# OM-02P.net
KiCad netlist of a schematic drawn in Altium Designer
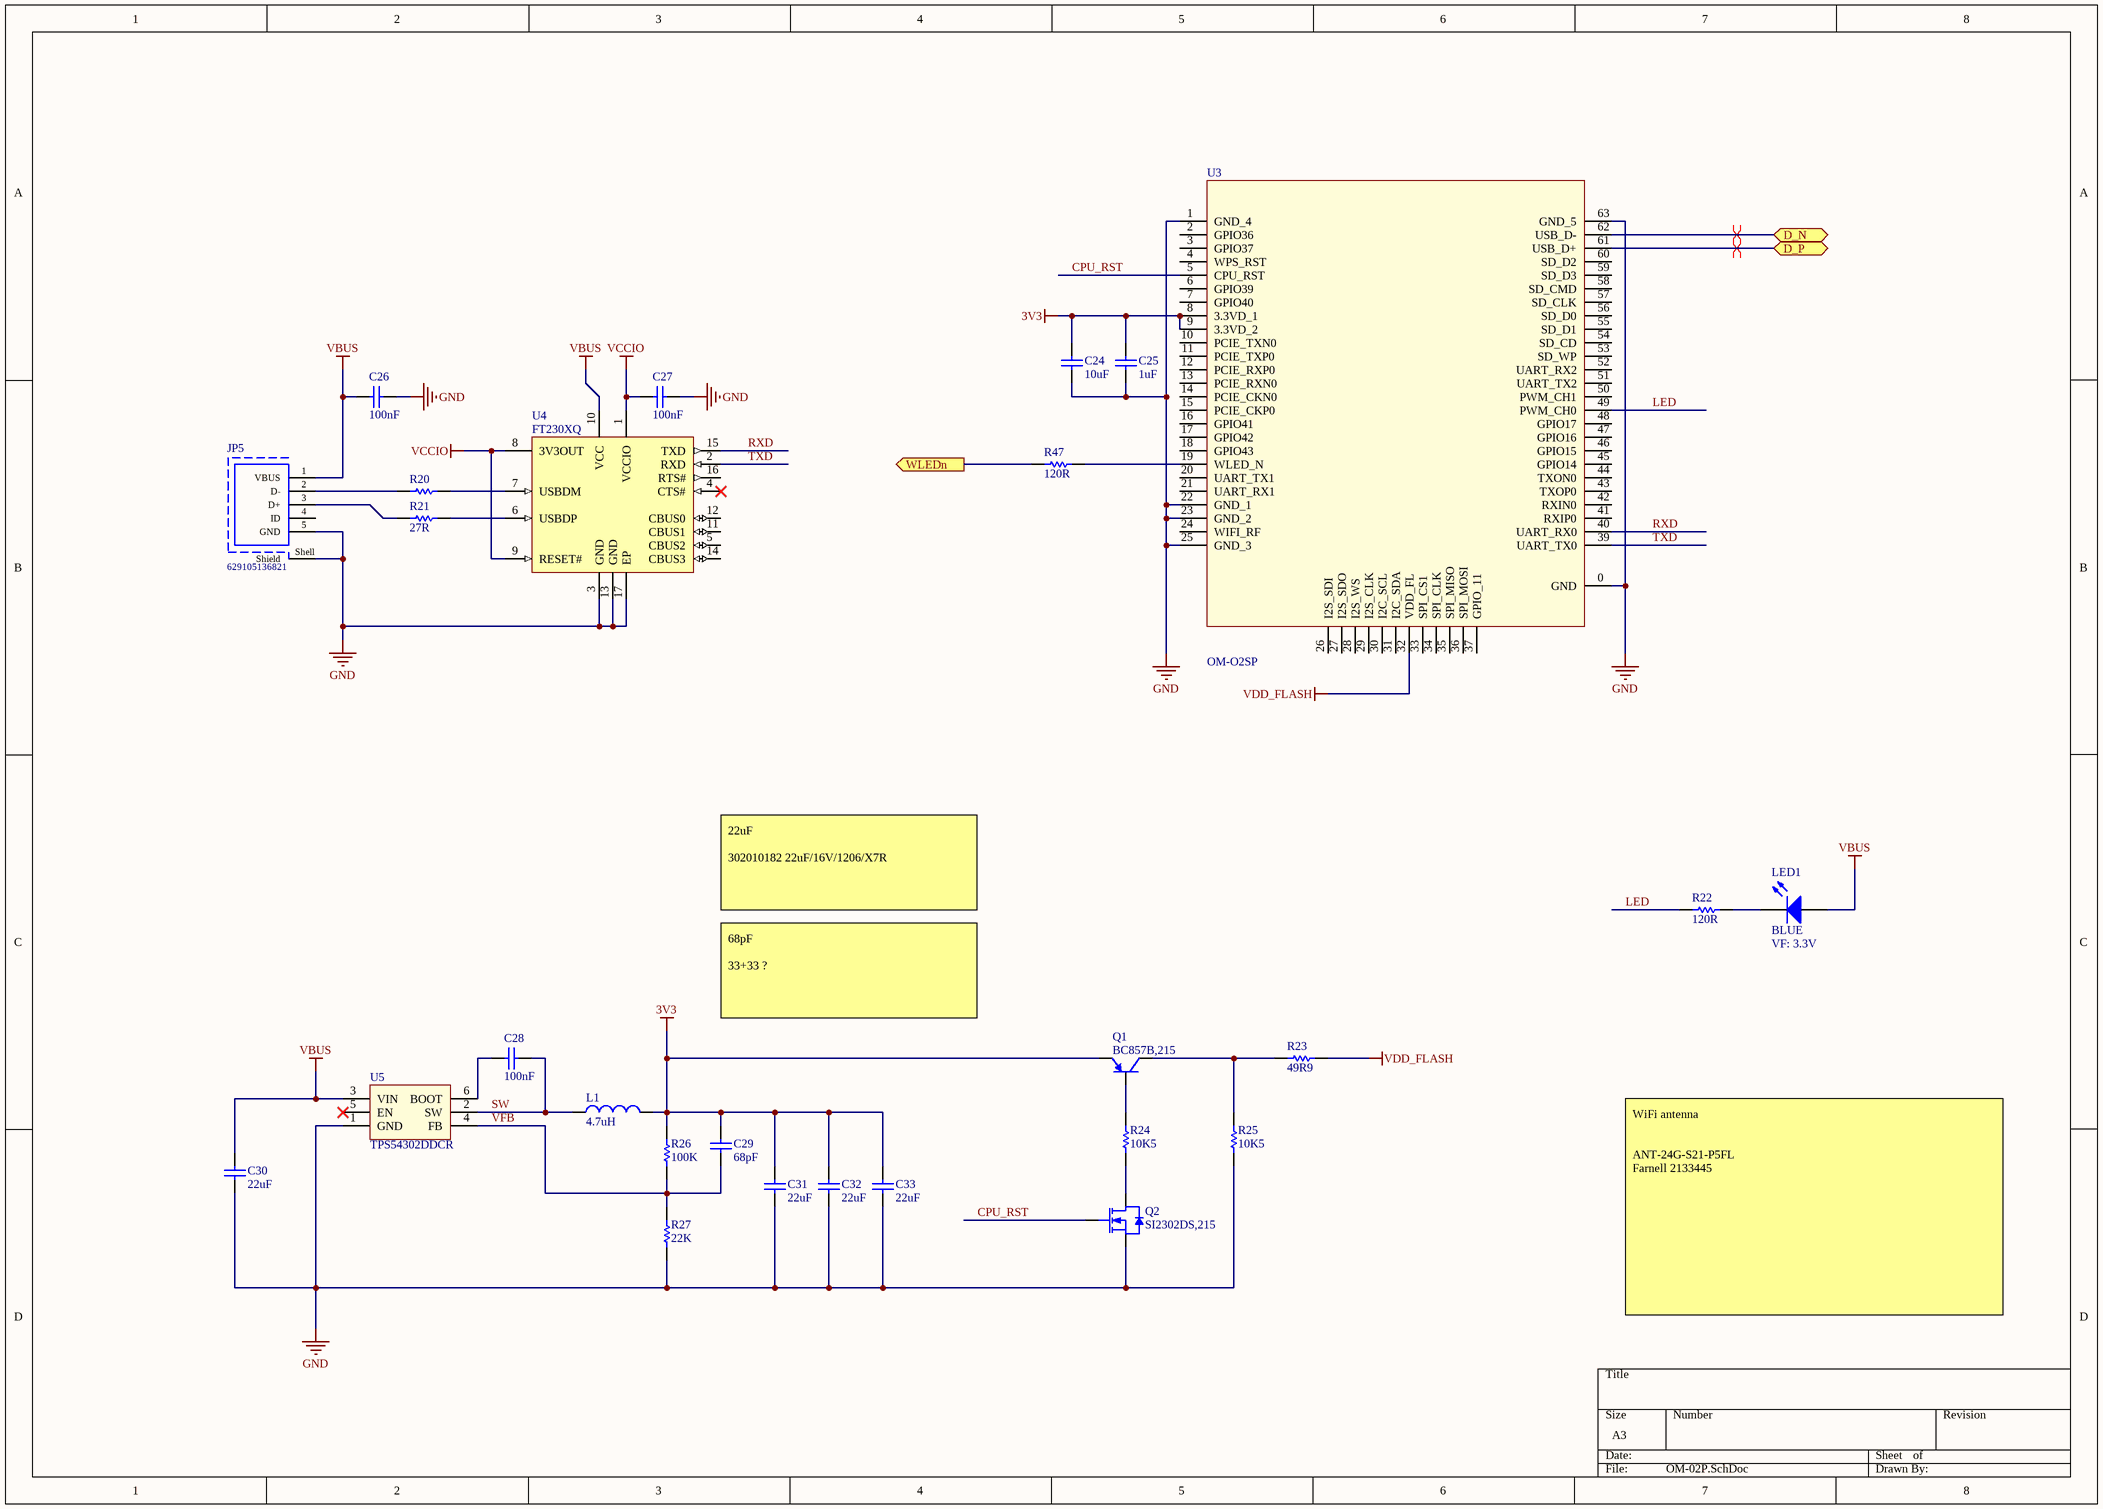
[diagram p0: OM-02P.SchDoc]

(export (version "E")
  (design (tool "Eeschema 10.0.6"))
  (components
    (comp (ref "C24")
      (value "10uF")
      (footprint "CAPC0603(1608)55_L")
      (description "0603 10uF ±20% 6.3V X5R H=0.8mm")
      (fields (field (name "MPN") "CL10A106MQ8NNNC") (field (name "VOLTAGE") "10V"))
      (libsource (lib "seeed") (part "CAP_10uF_0603"))
    )
    (comp (ref "C25")
      (value "1uF")
      (footprint "CAPC0402(1005)33_L")
      (description "0402 1μF ±10% 16V X5R")
      (fields (field (name "MPN") "GRM155R61C105KA12D") (field (name "VOLTAGE") "10V"))
      (libsource (lib "seeed") (part "CAP_1uF_0402"))
    )
    (comp (ref "C26")
      (value "100nF")
      (footprint "CAPC0402(1005)33_L")
      (description "0402 100nF ±10% 16V X5R")
      (fields (field (name "MPN") "GRM155R61C104KA88D") (field (name "VOLTAGE") "16V"))
      (libsource (lib "seeed") (part "CAP_100nF_0402"))
    )
    (comp (ref "C27")
      (value "100nF")
      (footprint "CAPC0402(1005)33_L")
      (description "0402 100nF ±10% 16V X5R")
      (fields (field (name "MPN") "GRM155R61C104KA88D") (field (name "VOLTAGE") "16V"))
      (libsource (lib "seeed") (part "CAP_100nF_0402"))
    )
    (comp (ref "C28")
      (value "100nF")
      (footprint "CAPC0402(1005)33_L")
      (description "0402 100nF ±10% 16V X5R")
      (fields (field (name "MPN") "GRM155R61C104KA88D") (field (name "VOLTAGE") "16V"))
      (libsource (lib "seeed") (part "CAP_100nF_0402"))
    )
    (comp (ref "C29")
      (value "68pF")
      (footprint "CAPC0402(1005)33_L")
      (description "0402 68pF ±5% 50V C0G")
      (fields (field (name "MPN") "GRM1555C1H680JA01D") (field (name "VOLTAGE") "50V"))
      (libsource (lib "seeed") (part "CAP_68pF_0402"))
    )
    (comp (ref "C30")
      (value "22uF")
      (footprint "CAPC1206(3216)75_L")
      (description "1206 22uF ±10% 16V X5R")
      (fields (field (name "MPN") "CL31A226KOHNNNE") (field (name "VOLTAGE") "16V"))
      (libsource (lib "seeed") (part "CAP_22uF_16V_1206"))
    )
    (comp (ref "C31")
      (value "22uF")
      (footprint "CAPC1206(3216)75_L")
      (description "1206 22uF ±10% 16V X5R")
      (fields (field (name "MPN") "CL31A226KOHNNNE") (field (name "VOLTAGE") "16V"))
      (libsource (lib "seeed") (part "CAP_22uF_16V_1206"))
    )
    (comp (ref "C32")
      (value "22uF")
      (footprint "CAPC1206(3216)75_L")
      (description "1206 22uF ±10% 16V X5R")
      (fields (field (name "MPN") "CL31A226KOHNNNE") (field (name "VOLTAGE") "16V"))
      (libsource (lib "seeed") (part "CAP_22uF_16V_1206"))
    )
    (comp (ref "C33")
      (value "22uF")
      (footprint "CAPC1206(3216)75_L")
      (description "1206 22uF ±10% 16V X5R")
      (fields (field (name "MPN") "CL31A226KOHNNNE") (field (name "VOLTAGE") "16V"))
      (libsource (lib "seeed") (part "CAP_22uF_16V_1206"))
    )
    (comp (ref "JP5")
      (value "629105136821")
      (footprint "629105136821")
      (description "Micro USB 2.0 Type B Receptacle WR-COM, Horizontal, SMT, with Pads and Pegs")
      (fields (field (name "PUBLISHER") "Wurth Elektronik"))
      (libsource (lib "ALTIUM-WR-COM_USB_20-rev18d") (part "629105136821"))
    )
    (comp (ref "L1")
      (value "4.7uH")
      (footprint "L_6045")
      (description "6.0*6.0*4.5 4.7μH ±20% 5.50A DCR=0.034 SRF=24MHz")
      (fields (field (name "MPN") "SWPA6045S4R7MT"))
      (libsource (lib "seeed") (part "L_4.7uH_6045"))
    )
    (comp (ref "LED1")
      (value "BLUE")
      (footprint "LED_APA3010x")
      (description "LED BLUE")
      (fields (field (name "MPN") "APA3010QBC/D-GX") (field (name "VF") "3.3V"))
      (libsource (lib "seeed") (part "LED-BLUE-APA3010QBC/D-GX"))
    )
    (comp (ref "Q1")
      (value "BC857B,215")
      (footprint "NXP-SOT23_L")
      (description "PNP,Vce=45V,Ic=0.1A,hfe=220~475")
      (fields (field (name "MANUFACTURER") "Infineon"))
      (libsource (lib "seeed") (part "BC857"))
    )
    (comp (ref "Q2")
      (value "SI2302DS,215")
      (footprint "NXP-SOT23_L")
      (description "N-Channel Enhancement Mode Field-Effect Transistor, 20 V, 2.5 A, 3-Pin SOT23, Tape and Reel")
      (fields (field (name "MANUFACTURER") "NXP Semiconductors") (field (name "MPN") "SI2302CDS-T1-GE3"))
      (libsource (lib "seeed") (part "SI2302"))
    )
    (comp (ref "R20")
      (value "27R")
      (footprint "RESC0402(1005)_L")
      (description "0402 27Ω ±1% 1/16W")
      (fields (field (name "TOLERANCE") "1%") (field (name "POWER") "62.5mW"))
      (libsource (lib "seeed") (part "RES_27R_0402"))
    )
    (comp (ref "R21")
      (value "27R")
      (footprint "RESC0402(1005)_L")
      (description "0402 27Ω ±1% 1/16W")
      (fields (field (name "TOLERANCE") "1%") (field (name "POWER") "62.5mW"))
      (libsource (lib "seeed") (part "RES_27R_0402"))
    )
    (comp (ref "R22")
      (value "120R")
      (footprint "RESC0402(1005)_L")
      (description "0402 120Ω ±1% 1/16W")
      (fields (field (name "TOLERANCE") "1%") (field (name "POWER") "62.5mW"))
      (libsource (lib "seeed") (part "RES_120R_0402"))
    )
    (comp (ref "R23")
      (value "49R9")
      (footprint "RESC0402(1005)_L")
      (description "0402 49.9Ω ±1% 1/16W")
      (fields (field (name "TOLERANCE") "1%") (field (name "POWER") "62.5mW"))
      (libsource (lib "seeed") (part "RES_49R9_0402"))
    )
    (comp (ref "R24")
      (value "10K5")
      (footprint "RESC0402(1005)_L")
      (description "0402 10.5KΩ ±1% 1/16W")
      (fields (field (name "TOLERANCE") "1%") (field (name "POWER") "62.5mW"))
      (libsource (lib "seeed") (part "RES_10K5_0402"))
    )
    (comp (ref "R25")
      (value "10K5")
      (footprint "RESC0402(1005)_L")
      (description "0402 10.5KΩ ±1% 1/16W")
      (fields (field (name "TOLERANCE") "1%") (field (name "POWER") "62.5mW"))
      (libsource (lib "seeed") (part "RES_10K5_0402"))
    )
    (comp (ref "R26")
      (value "100K")
      (footprint "RESC0402(1005)_L")
      (description "0402 100KΩ ±1% 1/16W")
      (fields (field (name "TOLERANCE") "1%") (field (name "POWER") "62.5mW"))
      (libsource (lib "seeed") (part "RES_100K_0402"))
    )
    (comp (ref "R27")
      (value "22K")
      (footprint "RESC0402(1005)_L")
      (description "0402 22KΩ ±1% 1/16W")
      (fields (field (name "TOLERANCE") "1%") (field (name "POWER") "62.5mW"))
      (libsource (lib "seeed") (part "RES_22K_0402"))
    )
    (comp (ref "R47")
      (value "120R")
      (footprint "RESC0402(1005)_L")
      (description "0402 120Ω ±1% 1/16W")
      (fields (field (name "TOLERANCE") "1%") (field (name "POWER") "62.5mW"))
      (libsource (lib "seeed") (part "RES_120R_0402"))
    )
    (comp (ref "U3")
      (value "OM-O2SP")
      (footprint "CPU-OM-O2S")
      (description "Onion Omega2S")
      (libsource (lib "micun") (part "CPU-OM-O2SP"))
    )
    (comp (ref "U4")
      (value "FT230XQ")
      (footprint "QFN-16_N")
      (description "USB Bridge, USB to UART USB 2.0 UART Interface 16-QFN (4x4)")
      (fields (field (name "MPN") "FT230XQ-R"))
      (libsource (lib "micun") (part "IC-COM-USB-FT230XQ-SQ17"))
    )
    (comp (ref "U5")
      (value "TPS54302DDCR")
      (footprint "FAIR-MA06A_V")
      (description "Buck Switching Regulator IC Positive Adjustable 0.596V 1 Output 3A SOT-23-6 Thin, TSOT-23-6")
      (libsource (lib "seeed") (part "TPS54302DDCR"))
    )
  )
  (nets
    (net (code "1") (name "/CPU_RST") (class "Default")
      (node (ref "Q2") (pin "1") (pinfunction "G_1") (pintype "passive"))
      (node (ref "U3") (pin "5") (pinfunction "CPU_RST_5") (pintype "passive"))
    )
    (net (code "2") (name "/D_N") (class "Default")
      (node (ref "U3") (pin "62") (pinfunction "USB_D-_62") (pintype "passive"))
    )
    (net (code "3") (name "/D_P") (class "Default")
      (node (ref "U3") (pin "61") (pinfunction "USB_D+_61") (pintype "passive"))
    )
    (net (code "4") (name "/LED") (class "Default")
      (node (ref "R22") (pin "1") (pinfunction "1_1") (pintype "passive"))
      (node (ref "U3") (pin "49") (pinfunction "PWM_CH0_49") (pintype "passive"))
    )
    (net (code "5") (name "/RXD") (class "Default")
      (node (ref "U3") (pin "40") (pinfunction "UART_RX0_40") (pintype "passive"))
      (node (ref "U4") (pin "15") (pinfunction "TXD_15") (pintype "output"))
    )
    (net (code "6") (name "/SW") (class "Default")
      (node (ref "C28") (pin "2") (pinfunction "2_2") (pintype "passive"))
      (node (ref "L1") (pin "1") (pinfunction "1_1") (pintype "passive"))
      (node (ref "U5") (pin "2") (pinfunction "SW_2") (pintype "passive"))
    )
    (net (code "7") (name "/TXD") (class "Default")
      (node (ref "U3") (pin "39") (pinfunction "UART_TX0_39") (pintype "passive"))
      (node (ref "U4") (pin "2") (pinfunction "RXD_2") (pintype "input"))
    )
    (net (code "8") (name "/VFB") (class "Default")
      (node (ref "C29") (pin "1") (pinfunction "1_1") (pintype "passive"))
      (node (ref "R26") (pin "1") (pinfunction "1_1") (pintype "passive"))
      (node (ref "R27") (pin "2") (pinfunction "2_2") (pintype "passive"))
      (node (ref "U5") (pin "4") (pinfunction "FB_4") (pintype "passive"))
    )
    (net (code "9") (name "/WLEDn") (class "Default")
      (node (ref "R47") (pin "1") (pinfunction "1_1") (pintype "passive"))
    )
    (net (code "10") (name "3V3") (class "Default")
      (node (ref "C24") (pin "2") (pinfunction "2_2") (pintype "passive"))
      (node (ref "C25") (pin "2") (pinfunction "2_2") (pintype "passive"))
      (node (ref "C29") (pin "2") (pinfunction "2_2") (pintype "passive"))
      (node (ref "C31") (pin "2") (pinfunction "2_2") (pintype "passive"))
      (node (ref "C32") (pin "2") (pinfunction "2_2") (pintype "passive"))
      (node (ref "C33") (pin "2") (pinfunction "2_2") (pintype "passive"))
      (node (ref "L1") (pin "2") (pinfunction "2_2") (pintype "passive"))
      (node (ref "Q1") (pin "2") (pinfunction "E_2") (pintype "passive"))
      (node (ref "R26") (pin "2") (pinfunction "2_2") (pintype "passive"))
      (node (ref "U3") (pin "8") (pinfunction "3.3VD_1_8") (pintype "power_in"))
      (node (ref "U3") (pin "9") (pinfunction "3.3VD_2_9") (pintype "power_in"))
    )
    (net (code "11") (name "GND") (class "Default")
      (node (ref "C24") (pin "1") (pinfunction "1_1") (pintype "passive"))
      (node (ref "C25") (pin "1") (pinfunction "1_1") (pintype "passive"))
      (node (ref "C26") (pin "2") (pinfunction "2_2") (pintype "passive"))
      (node (ref "C27") (pin "2") (pinfunction "2_2") (pintype "passive"))
      (node (ref "C30") (pin "1") (pinfunction "1_1") (pintype "passive"))
      (node (ref "C31") (pin "1") (pinfunction "1_1") (pintype "passive"))
      (node (ref "C32") (pin "1") (pinfunction "1_1") (pintype "passive"))
      (node (ref "C33") (pin "1") (pinfunction "1_1") (pintype "passive"))
      (node (ref "JP5") (pin "5") (pinfunction "GND_5") (pintype "passive"))
      (node (ref "JP5") (pin "Shell") (pinfunction "Shield_Shell") (pintype "passive"))
      (node (ref "Q2") (pin "2") (pinfunction "S_2") (pintype "passive"))
      (node (ref "R25") (pin "1") (pinfunction "1_1") (pintype "passive"))
      (node (ref "R27") (pin "1") (pinfunction "1_1") (pintype "passive"))
      (node (ref "U3") (pin "0") (pinfunction "GND_0") (pintype "passive"))
      (node (ref "U3") (pin "1") (pinfunction "GND_4_1") (pintype "power_in"))
      (node (ref "U3") (pin "22") (pinfunction "GND_1_22") (pintype "power_in"))
      (node (ref "U3") (pin "23") (pinfunction "GND_2_23") (pintype "power_in"))
      (node (ref "U3") (pin "25") (pinfunction "GND_3_25") (pintype "power_in"))
      (node (ref "U3") (pin "63") (pinfunction "GND_5_63") (pintype "power_in"))
      (node (ref "U4") (pin "13") (pinfunction "GND_13") (pintype "power_in"))
      (node (ref "U4") (pin "17") (pinfunction "EP_17") (pintype "power_in"))
      (node (ref "U4") (pin "3") (pinfunction "GND_3") (pintype "power_in"))
      (node (ref "U5") (pin "1") (pinfunction "GND_1") (pintype "power_in"))
    )
    (net (code "12") (name "Net-(JP5-D+)") (class "Default")
      (node (ref "JP5") (pin "3") (pinfunction "D+_3") (pintype "passive"))
      (node (ref "R21") (pin "1") (pinfunction "1_1") (pintype "passive"))
    )
    (net (code "13") (name "Net-(JP5-D-)") (class "Default")
      (node (ref "JP5") (pin "2") (pinfunction "D-_2") (pintype "passive"))
      (node (ref "R20") (pin "1") (pinfunction "1_1") (pintype "passive"))
    )
    (net (code "14") (name "Net-(LED1-K)") (class "Default")
      (node (ref "LED1") (pin "1") (pinfunction "K_1") (pintype "passive"))
      (node (ref "R22") (pin "2") (pinfunction "2_2") (pintype "passive"))
    )
    (net (code "15") (name "Net-(Q1-B)") (class "Default")
      (node (ref "Q1") (pin "1") (pinfunction "B_1") (pintype "passive"))
      (node (ref "R24") (pin "2") (pinfunction "2_2") (pintype "passive"))
    )
    (net (code "16") (name "Net-(Q1-C)") (class "Default")
      (node (ref "Q1") (pin "3") (pinfunction "C_3") (pintype "passive"))
      (node (ref "R23") (pin "1") (pinfunction "1_1") (pintype "passive"))
      (node (ref "R25") (pin "2") (pinfunction "2_2") (pintype "passive"))
    )
    (net (code "17") (name "Net-(Q2-D)") (class "Default")
      (node (ref "Q2") (pin "3") (pinfunction "D_3") (pintype "passive"))
      (node (ref "R24") (pin "1") (pinfunction "1_1") (pintype "passive"))
    )
    (net (code "18") (name "Net-(U3-WLED_N)") (class "Default")
      (node (ref "R47") (pin "2") (pinfunction "2_2") (pintype "passive"))
      (node (ref "U3") (pin "19") (pinfunction "WLED_N_19") (pintype "passive"))
    )
    (net (code "19") (name "Net-(U4-USBDM)") (class "Default")
      (node (ref "R20") (pin "2") (pinfunction "2_2") (pintype "passive"))
      (node (ref "U4") (pin "7") (pinfunction "USBDM_7") (pintype "input"))
    )
    (net (code "20") (name "Net-(U4-USBDP)") (class "Default")
      (node (ref "R21") (pin "2") (pinfunction "2_2") (pintype "passive"))
      (node (ref "U4") (pin "6") (pinfunction "USBDP_6") (pintype "input"))
    )
    (net (code "21") (name "Net-(U5-BOOT)") (class "Default")
      (node (ref "C28") (pin "1") (pinfunction "1_1") (pintype "passive"))
      (node (ref "U5") (pin "6") (pinfunction "BOOT_6") (pintype "power_in"))
    )
    (net (code "22") (name "VBUS") (class "Default")
      (node (ref "C26") (pin "1") (pinfunction "1_1") (pintype "passive"))
      (node (ref "C30") (pin "2") (pinfunction "2_2") (pintype "passive"))
      (node (ref "JP5") (pin "1") (pinfunction "VBUS_1") (pintype "passive"))
      (node (ref "LED1") (pin "2") (pinfunction "A_2") (pintype "passive"))
      (node (ref "U4") (pin "10") (pinfunction "VCC_10") (pintype "power_in"))
      (node (ref "U5") (pin "3") (pinfunction "VIN_3") (pintype "power_in"))
    )
    (net (code "23") (name "VCCIO") (class "Default")
      (node (ref "C27") (pin "1") (pinfunction "1_1") (pintype "passive"))
      (node (ref "U4") (pin "1") (pinfunction "VCCIO_1") (pintype "power_in"))
      (node (ref "U4") (pin "8") (pinfunction "3V3OUT_8") (pintype "power_in"))
      (node (ref "U4") (pin "9") (pinfunction "RESET#_9") (pintype "input"))
    )
    (net (code "24") (name "VDD_FLASH") (class "Default")
      (node (ref "R23") (pin "2") (pinfunction "2_2") (pintype "passive"))
      (node (ref "U3") (pin "32") (pinfunction "VDD_FL_32") (pintype "power_in"))
    )
    (net (code "25") (name "unconnected-(JP5-ID-Pad4)") (class "Default")
      (node (ref "JP5") (pin "4") (pinfunction "ID_4") (pintype "passive"))
    )
    (net (code "26") (name "unconnected-(U3-GPIO14-Pad45)") (class "Default")
      (node (ref "U3") (pin "45") (pinfunction "GPIO14_45") (pintype "passive"))
    )
    (net (code "27") (name "unconnected-(U3-GPIO15-Pad46)") (class "Default")
      (node (ref "U3") (pin "46") (pinfunction "GPIO15_46") (pintype "passive"))
    )
    (net (code "28") (name "unconnected-(U3-GPIO16-Pad47)") (class "Default")
      (node (ref "U3") (pin "47") (pinfunction "GPIO16_47") (pintype "passive"))
    )
    (net (code "29") (name "unconnected-(U3-GPIO17-Pad48)") (class "Default")
      (node (ref "U3") (pin "48") (pinfunction "GPIO17_48") (pintype "passive"))
    )
    (net (code "30") (name "unconnected-(U3-GPIO36-Pad2)") (class "Default")
      (node (ref "U3") (pin "2") (pinfunction "GPIO36_2") (pintype "passive"))
    )
    (net (code "31") (name "unconnected-(U3-GPIO37-Pad3)") (class "Default")
      (node (ref "U3") (pin "3") (pinfunction "GPIO37_3") (pintype "passive"))
    )
    (net (code "32") (name "unconnected-(U3-GPIO39-Pad6)") (class "Default")
      (node (ref "U3") (pin "6") (pinfunction "GPIO39_6") (pintype "passive"))
    )
    (net (code "33") (name "unconnected-(U3-GPIO40-Pad7)") (class "Default")
      (node (ref "U3") (pin "7") (pinfunction "GPIO40_7") (pintype "passive"))
    )
    (net (code "34") (name "unconnected-(U3-GPIO41-Pad16)") (class "Default")
      (node (ref "U3") (pin "16") (pinfunction "GPIO41_16") (pintype "passive"))
    )
    (net (code "35") (name "unconnected-(U3-GPIO42-Pad17)") (class "Default")
      (node (ref "U3") (pin "17") (pinfunction "GPIO42_17") (pintype "passive"))
    )
    (net (code "36") (name "unconnected-(U3-GPIO43-Pad18)") (class "Default")
      (node (ref "U3") (pin "18") (pinfunction "GPIO43_18") (pintype "passive"))
    )
    (net (code "37") (name "unconnected-(U3-GPIO_11-Pad37)") (class "Default")
      (node (ref "U3") (pin "37") (pinfunction "GPIO_11_37") (pintype "passive"))
    )
    (net (code "38") (name "unconnected-(U3-I2C_SCL-Pad30)") (class "Default")
      (node (ref "U3") (pin "30") (pinfunction "I2C_SCL_30") (pintype "passive"))
    )
    (net (code "39") (name "unconnected-(U3-I2C_SDA-Pad31)") (class "Default")
      (node (ref "U3") (pin "31") (pinfunction "I2C_SDA_31") (pintype "passive"))
    )
    (net (code "40") (name "unconnected-(U3-I2S_CLK-Pad29)") (class "Default")
      (node (ref "U3") (pin "29") (pinfunction "I2S_CLK_29") (pintype "passive"))
    )
    (net (code "41") (name "unconnected-(U3-I2S_SDI-Pad26)") (class "Default")
      (node (ref "U3") (pin "26") (pinfunction "I2S_SDI_26") (pintype "passive"))
    )
    (net (code "42") (name "unconnected-(U3-I2S_SDO-Pad27)") (class "Default")
      (node (ref "U3") (pin "27") (pinfunction "I2S_SDO_27") (pintype "passive"))
    )
    (net (code "43") (name "unconnected-(U3-I2S_WS-Pad28)") (class "Default")
      (node (ref "U3") (pin "28") (pinfunction "I2S_WS_28") (pintype "passive"))
    )
    (net (code "44") (name "unconnected-(U3-PCIE_CKN0-Pad14)") (class "Default")
      (node (ref "U3") (pin "14") (pinfunction "PCIE_CKN0_14") (pintype "passive"))
    )
    (net (code "45") (name "unconnected-(U3-PCIE_CKP0-Pad15)") (class "Default")
      (node (ref "U3") (pin "15") (pinfunction "PCIE_CKP0_15") (pintype "passive"))
    )
    (net (code "46") (name "unconnected-(U3-PCIE_RXN0-Pad13)") (class "Default")
      (node (ref "U3") (pin "13") (pinfunction "PCIE_RXN0_13") (pintype "passive"))
    )
    (net (code "47") (name "unconnected-(U3-PCIE_RXP0-Pad12)") (class "Default")
      (node (ref "U3") (pin "12") (pinfunction "PCIE_RXP0_12") (pintype "passive"))
    )
    (net (code "48") (name "unconnected-(U3-PCIE_TXN0-Pad10)") (class "Default")
      (node (ref "U3") (pin "10") (pinfunction "PCIE_TXN0_10") (pintype "passive"))
    )
    (net (code "49") (name "unconnected-(U3-PCIE_TXP0-Pad11)") (class "Default")
      (node (ref "U3") (pin "11") (pinfunction "PCIE_TXP0_11") (pintype "passive"))
    )
    (net (code "50") (name "unconnected-(U3-PWM_CH1-Pad50)") (class "Default")
      (node (ref "U3") (pin "50") (pinfunction "PWM_CH1_50") (pintype "passive"))
    )
    (net (code "51") (name "unconnected-(U3-RXIN0-Pad42)") (class "Default")
      (node (ref "U3") (pin "42") (pinfunction "RXIN0_42") (pintype "passive"))
    )
    (net (code "52") (name "unconnected-(U3-RXIP0-Pad41)") (class "Default")
      (node (ref "U3") (pin "41") (pinfunction "RXIP0_41") (pintype "passive"))
    )
    (net (code "53") (name "unconnected-(U3-SD_CD-Pad54)") (class "Default")
      (node (ref "U3") (pin "54") (pinfunction "SD_CD_54") (pintype "passive"))
    )
    (net (code "54") (name "unconnected-(U3-SD_CLK-Pad57)") (class "Default")
      (node (ref "U3") (pin "57") (pinfunction "SD_CLK_57") (pintype "passive"))
    )
    (net (code "55") (name "unconnected-(U3-SD_CMD-Pad58)") (class "Default")
      (node (ref "U3") (pin "58") (pinfunction "SD_CMD_58") (pintype "passive"))
    )
    (net (code "56") (name "unconnected-(U3-SD_D0-Pad56)") (class "Default")
      (node (ref "U3") (pin "56") (pinfunction "SD_D0_56") (pintype "passive"))
    )
    (net (code "57") (name "unconnected-(U3-SD_D1-Pad55)") (class "Default")
      (node (ref "U3") (pin "55") (pinfunction "SD_D1_55") (pintype "passive"))
    )
    (net (code "58") (name "unconnected-(U3-SD_D2-Pad60)") (class "Default")
      (node (ref "U3") (pin "60") (pinfunction "SD_D2_60") (pintype "passive"))
    )
    (net (code "59") (name "unconnected-(U3-SD_D3-Pad59)") (class "Default")
      (node (ref "U3") (pin "59") (pinfunction "SD_D3_59") (pintype "passive"))
    )
    (net (code "60") (name "unconnected-(U3-SD_WP-Pad53)") (class "Default")
      (node (ref "U3") (pin "53") (pinfunction "SD_WP_53") (pintype "passive"))
    )
    (net (code "61") (name "unconnected-(U3-SPI_CLK-Pad34)") (class "Default")
      (node (ref "U3") (pin "34") (pinfunction "SPI_CLK_34") (pintype "passive"))
    )
    (net (code "62") (name "unconnected-(U3-SPI_CS1-Pad33)") (class "Default")
      (node (ref "U3") (pin "33") (pinfunction "SPI_CS1_33") (pintype "passive"))
    )
    (net (code "63") (name "unconnected-(U3-SPI_MISO-Pad35)") (class "Default")
      (node (ref "U3") (pin "35") (pinfunction "SPI_MISO_35") (pintype "passive"))
    )
    (net (code "64") (name "unconnected-(U3-SPI_MOSI-Pad36)") (class "Default")
      (node (ref "U3") (pin "36") (pinfunction "SPI_MOSI_36") (pintype "passive"))
    )
    (net (code "65") (name "unconnected-(U3-TXON0-Pad44)") (class "Default")
      (node (ref "U3") (pin "44") (pinfunction "TXON0_44") (pintype "passive"))
    )
    (net (code "66") (name "unconnected-(U3-TXOP0-Pad43)") (class "Default")
      (node (ref "U3") (pin "43") (pinfunction "TXOP0_43") (pintype "passive"))
    )
    (net (code "67") (name "unconnected-(U3-UART_RX1-Pad21)") (class "Default")
      (node (ref "U3") (pin "21") (pinfunction "UART_RX1_21") (pintype "passive"))
    )
    (net (code "68") (name "unconnected-(U3-UART_RX2-Pad52)") (class "Default")
      (node (ref "U3") (pin "52") (pinfunction "UART_RX2_52") (pintype "passive"))
    )
    (net (code "69") (name "unconnected-(U3-UART_TX1-Pad20)") (class "Default")
      (node (ref "U3") (pin "20") (pinfunction "UART_TX1_20") (pintype "passive"))
    )
    (net (code "70") (name "unconnected-(U3-UART_TX2-Pad51)") (class "Default")
      (node (ref "U3") (pin "51") (pinfunction "UART_TX2_51") (pintype "passive"))
    )
    (net (code "71") (name "unconnected-(U3-WIFI_RF-Pad24)") (class "Default")
      (node (ref "U3") (pin "24") (pinfunction "WIFI_RF_24") (pintype "passive"))
    )
    (net (code "72") (name "unconnected-(U3-WPS_RST-Pad4)") (class "Default")
      (node (ref "U3") (pin "4") (pinfunction "WPS_RST_4") (pintype "passive"))
    )
    (net (code "73") (name "unconnected-(U4-CBUS0-Pad12)") (class "Default")
      (node (ref "U4") (pin "12") (pinfunction "CBUS0_12") (pintype "bidirectional"))
    )
    (net (code "74") (name "unconnected-(U4-CBUS1-Pad11)") (class "Default")
      (node (ref "U4") (pin "11") (pinfunction "CBUS1_11") (pintype "bidirectional"))
    )
    (net (code "75") (name "unconnected-(U4-CBUS2-Pad5)") (class "Default")
      (node (ref "U4") (pin "5") (pinfunction "CBUS2_5") (pintype "bidirectional"))
    )
    (net (code "76") (name "unconnected-(U4-CBUS3-Pad14)") (class "Default")
      (node (ref "U4") (pin "14") (pinfunction "CBUS3_14") (pintype "bidirectional"))
    )
    (net (code "77") (name "unconnected-(U4-CTS#-Pad4)") (class "Default")
      (node (ref "U4") (pin "4") (pinfunction "CTS#_4") (pintype "input+no_connect"))
    )
    (net (code "78") (name "unconnected-(U4-RTS#-Pad16)") (class "Default")
      (node (ref "U4") (pin "16") (pinfunction "RTS#_16") (pintype "output"))
    )
    (net (code "79") (name "unconnected-(U5-EN-Pad5)") (class "Default")
      (node (ref "U5") (pin "5") (pinfunction "EN_5") (pintype "passive+no_connect"))
    )
  )
)
